# RPI_drawing.net
KiCad netlist of a schematic drawn in Altium Designer
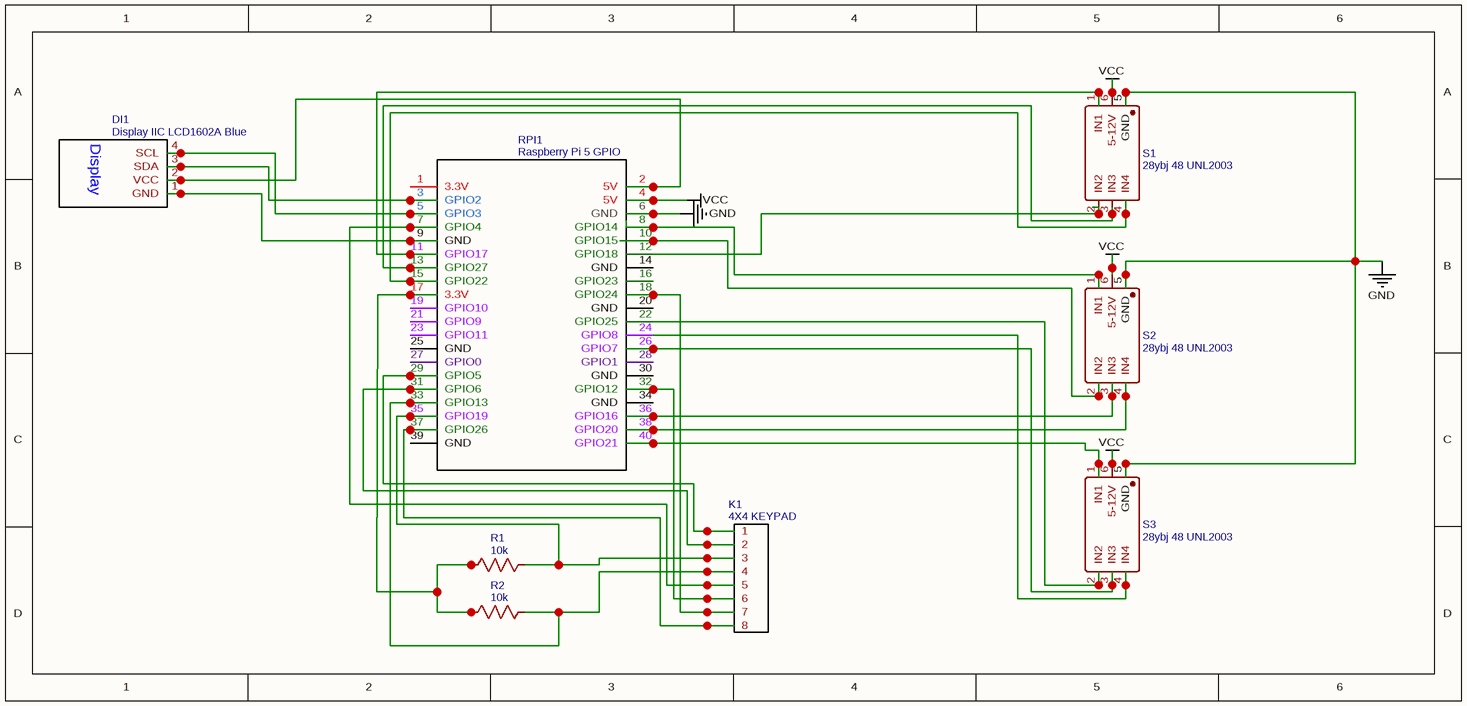
[diagram p0: RPI_drawing.schdoc]

(export (version "E")
  (design (tool "Eeschema 10.0.6"))
  (components
    (comp (ref "DI1")
      (value "Display IIC LCD1602A Blue")
      (fields (field (name "CONTRIBUTOR") "ziclope"))
      (libsource (lib "altium-import") (part "root_2_Display IIC LCD1602A Blue_"))
    )
    (comp (ref "K1")
      (value "4X4 KEYPAD")
      (fields (field (name "CONTRIBUTOR") "hasbifajrul03"))
      (libsource (lib "altium-import") (part "root_3_4X4 KEYPAD_"))
    )
    (comp (ref "R1")
      (value "10k")
      (fields (field (name "CONTRIBUTOR") "LCEDA_Lib"))
      (libsource (lib "altium-import") (part "root_0_10k_"))
    )
    (comp (ref "R2")
      (value "10k")
      (fields (field (name "CONTRIBUTOR") "LCEDA_Lib"))
      (libsource (lib "altium-import") (part "root_0_10k_"))
    )
    (comp (ref "RPI1")
      (value "Raspberry Pi 5 GPIO")
      (fields
        (field (name "MANUFACTURER") "Raspberry Pi 5 4GB")
        (field (name "CONTRIBUTOR") "marcus06second")
      )
      (libsource (lib "altium-import") (part "root_0_Raspberry Pi 5 GPIO_"))
    )
    (comp (ref "S1")
      (value "28ybj 48 UNL2003")
      (fields (field (name "CONTRIBUTOR") "amenard"))
      (libsource (lib "altium-import") (part "root_3_28ybj 48 UNL2003_"))
    )
    (comp (ref "S2")
      (value "28ybj 48 UNL2003")
      (fields (field (name "CONTRIBUTOR") "amenard"))
      (libsource (lib "altium-import") (part "root_3_28ybj 48 UNL2003_"))
    )
    (comp (ref "S3")
      (value "28ybj 48 UNL2003")
      (fields (field (name "CONTRIBUTOR") "amenard"))
      (libsource (lib "altium-import") (part "root_3_28ybj 48 UNL2003_"))
    )
  )
  (nets
    (net (code "1") (name "GND") (class "Default")
      (node (ref "RPI1") (pin "6") (pinfunction "GND_6") (pintype "passive"))
      (node (ref "S1") (pin "5") (pinfunction "GND_5") (pintype "passive"))
      (node (ref "S2") (pin "5") (pinfunction "GND_5") (pintype "passive"))
      (node (ref "S3") (pin "5") (pinfunction "GND_5") (pintype "passive"))
    )
    (net (code "2") (name "Net-(DI1-GND)") (class "Default")
      (node (ref "DI1") (pin "1") (pinfunction "GND_1") (pintype "passive"))
      (node (ref "RPI1") (pin "9") (pinfunction "GND_9") (pintype "passive"))
    )
    (net (code "3") (name "Net-(DI1-SCL)") (class "Default")
      (node (ref "DI1") (pin "4") (pinfunction "SCL_4") (pintype "passive"))
      (node (ref "RPI1") (pin "5") (pinfunction "GPIO3_5") (pintype "passive"))
    )
    (net (code "4") (name "Net-(DI1-SDA)") (class "Default")
      (node (ref "DI1") (pin "3") (pinfunction "SDA_3") (pintype "passive"))
      (node (ref "RPI1") (pin "3") (pinfunction "GPIO2_3") (pintype "passive"))
    )
    (net (code "5") (name "Net-(DI1-VCC)") (class "Default")
      (node (ref "DI1") (pin "2") (pinfunction "VCC_2") (pintype "passive"))
      (node (ref "RPI1") (pin "2") (pinfunction "5V_2") (pintype "passive"))
    )
    (net (code "6") (name "Net-(K1-1)") (class "Default")
      (node (ref "K1") (pin "3") (pinfunction "1_3") (pintype "passive"))
      (node (ref "RPI1") (pin "29") (pinfunction "GPIO5_29") (pintype "passive"))
    )
    (net (code "7") (name "Net-(K1-2)") (class "Default")
      (node (ref "K1") (pin "4") (pinfunction "2_4") (pintype "passive"))
      (node (ref "RPI1") (pin "31") (pinfunction "GPIO6_31") (pintype "passive"))
    )
    (net (code "8") (name "Net-(K1-3)") (class "Default")
      (node (ref "K1") (pin "5") (pinfunction "3_5") (pintype "passive"))
      (node (ref "R1") (pin "2") (pinfunction "2_2") (pintype "passive"))
      (node (ref "RPI1") (pin "35") (pinfunction "GPIO19_35") (pintype "passive"))
    )
    (net (code "9") (name "Net-(K1-4)") (class "Default")
      (node (ref "K1") (pin "6") (pinfunction "4_6") (pintype "passive"))
      (node (ref "R2") (pin "2") (pinfunction "2_2") (pintype "passive"))
      (node (ref "RPI1") (pin "33") (pinfunction "GPIO13_33") (pintype "passive"))
    )
    (net (code "10") (name "Net-(K1-5)") (class "Default")
      (node (ref "K1") (pin "7") (pinfunction "5_7") (pintype "passive"))
      (node (ref "RPI1") (pin "7") (pinfunction "GPIO4_7") (pintype "passive"))
    )
    (net (code "11") (name "Net-(K1-6)") (class "Default")
      (node (ref "K1") (pin "8") (pinfunction "6_8") (pintype "passive"))
      (node (ref "RPI1") (pin "32") (pinfunction "GPIO12_32") (pintype "passive"))
    )
    (net (code "12") (name "Net-(K1-7)") (class "Default")
      (node (ref "K1") (pin "9") (pinfunction "7_9") (pintype "passive"))
      (node (ref "RPI1") (pin "18") (pinfunction "GPIO24_18") (pintype "passive"))
    )
    (net (code "13") (name "Net-(K1-8)") (class "Default")
      (node (ref "K1") (pin "10") (pinfunction "8_10") (pintype "passive"))
      (node (ref "RPI1") (pin "37") (pinfunction "GPIO26_37") (pintype "passive"))
    )
    (net (code "14") (name "Net-(R1-Pad1)") (class "Default")
      (node (ref "R1") (pin "1") (pinfunction "1_1") (pintype "passive"))
      (node (ref "R2") (pin "1") (pinfunction "1_1") (pintype "passive"))
      (node (ref "RPI1") (pin "17") (pinfunction "3.3V_17") (pintype "passive"))
    )
    (net (code "15") (name "Net-(RPI1-GPIO7)") (class "Default")
      (node (ref "RPI1") (pin "26") (pinfunction "GPIO7_26") (pintype "passive"))
      (node (ref "S3") (pin "3") (pinfunction "IN3_3") (pintype "passive"))
    )
    (net (code "16") (name "Net-(RPI1-GPIO8)") (class "Default")
      (node (ref "RPI1") (pin "24") (pinfunction "GPIO8_24") (pintype "passive"))
      (node (ref "S3") (pin "4") (pinfunction "IN4_4") (pintype "passive"))
    )
    (net (code "17") (name "Net-(RPI1-GPIO14)") (class "Default")
      (node (ref "RPI1") (pin "8") (pinfunction "GPIO14_8") (pintype "passive"))
      (node (ref "S2") (pin "1") (pinfunction "IN1_1") (pintype "passive"))
    )
    (net (code "18") (name "Net-(RPI1-GPIO15)") (class "Default")
      (node (ref "RPI1") (pin "10") (pinfunction "GPIO15_10") (pintype "passive"))
      (node (ref "S2") (pin "2") (pinfunction "IN2_2") (pintype "passive"))
    )
    (net (code "19") (name "Net-(RPI1-GPIO16)") (class "Default")
      (node (ref "RPI1") (pin "36") (pinfunction "GPIO16_36") (pintype "passive"))
      (node (ref "S2") (pin "3") (pinfunction "IN3_3") (pintype "passive"))
    )
    (net (code "20") (name "Net-(RPI1-GPIO17)") (class "Default")
      (node (ref "RPI1") (pin "11") (pinfunction "GPIO17_11") (pintype "passive"))
      (node (ref "S1") (pin "1") (pinfunction "IN1_1") (pintype "passive"))
    )
    (net (code "21") (name "Net-(RPI1-GPIO18)") (class "Default")
      (node (ref "RPI1") (pin "12") (pinfunction "GPIO18_12") (pintype "passive"))
      (node (ref "S1") (pin "2") (pinfunction "IN2_2") (pintype "passive"))
    )
    (net (code "22") (name "Net-(RPI1-GPIO20)") (class "Default")
      (node (ref "RPI1") (pin "38") (pinfunction "GPIO20_38") (pintype "passive"))
      (node (ref "S2") (pin "4") (pinfunction "IN4_4") (pintype "passive"))
    )
    (net (code "23") (name "Net-(RPI1-GPIO21)") (class "Default")
      (node (ref "RPI1") (pin "40") (pinfunction "GPIO21_40") (pintype "passive"))
      (node (ref "S3") (pin "1") (pinfunction "IN1_1") (pintype "passive"))
    )
    (net (code "24") (name "Net-(RPI1-GPIO22)") (class "Default")
      (node (ref "RPI1") (pin "15") (pinfunction "GPIO22_15") (pintype "passive"))
      (node (ref "S1") (pin "4") (pinfunction "IN4_4") (pintype "passive"))
    )
    (net (code "25") (name "Net-(RPI1-GPIO25)") (class "Default")
      (node (ref "RPI1") (pin "22") (pinfunction "GPIO25_22") (pintype "passive"))
      (node (ref "S3") (pin "2") (pinfunction "IN2_2") (pintype "passive"))
    )
    (net (code "26") (name "Net-(RPI1-GPIO27)") (class "Default")
      (node (ref "RPI1") (pin "13") (pinfunction "GPIO27_13") (pintype "passive"))
      (node (ref "S1") (pin "3") (pinfunction "IN3_3") (pintype "passive"))
    )
    (net (code "27") (name "VCC") (class "Default")
      (node (ref "RPI1") (pin "4") (pinfunction "5V_4") (pintype "passive"))
      (node (ref "S1") (pin "6") (pinfunction "5-12V_6") (pintype "passive"))
      (node (ref "S2") (pin "6") (pinfunction "5-12V_6") (pintype "passive"))
      (node (ref "S3") (pin "6") (pinfunction "5-12V_6") (pintype "passive"))
    )
    (net (code "28") (name "unconnected-(RPI1-3.3V-Pad1)") (class "Default")
      (node (ref "RPI1") (pin "1") (pinfunction "3.3V_1") (pintype "passive"))
    )
    (net (code "29") (name "unconnected-(RPI1-GND-Pad14)") (class "Default")
      (node (ref "RPI1") (pin "14") (pinfunction "GND_14") (pintype "passive"))
    )
    (net (code "30") (name "unconnected-(RPI1-GND-Pad20)") (class "Default")
      (node (ref "RPI1") (pin "20") (pinfunction "GND_20") (pintype "passive"))
    )
    (net (code "31") (name "unconnected-(RPI1-GND-Pad25)") (class "Default")
      (node (ref "RPI1") (pin "25") (pinfunction "GND_25") (pintype "passive"))
    )
    (net (code "32") (name "unconnected-(RPI1-GND-Pad30)") (class "Default")
      (node (ref "RPI1") (pin "30") (pinfunction "GND_30") (pintype "passive"))
    )
    (net (code "33") (name "unconnected-(RPI1-GND-Pad34)") (class "Default")
      (node (ref "RPI1") (pin "34") (pinfunction "GND_34") (pintype "passive"))
    )
    (net (code "34") (name "unconnected-(RPI1-GND-Pad39)") (class "Default")
      (node (ref "RPI1") (pin "39") (pinfunction "GND_39") (pintype "passive"))
    )
    (net (code "35") (name "unconnected-(RPI1-GPIO0-Pad27)") (class "Default")
      (node (ref "RPI1") (pin "27") (pinfunction "GPIO0_27") (pintype "passive"))
    )
    (net (code "36") (name "unconnected-(RPI1-GPIO1-Pad28)") (class "Default")
      (node (ref "RPI1") (pin "28") (pinfunction "GPIO1_28") (pintype "passive"))
    )
    (net (code "37") (name "unconnected-(RPI1-GPIO9-Pad21)") (class "Default")
      (node (ref "RPI1") (pin "21") (pinfunction "GPIO9_21") (pintype "passive"))
    )
    (net (code "38") (name "unconnected-(RPI1-GPIO10-Pad19)") (class "Default")
      (node (ref "RPI1") (pin "19") (pinfunction "GPIO10_19") (pintype "passive"))
    )
    (net (code "39") (name "unconnected-(RPI1-GPIO11-Pad23)") (class "Default")
      (node (ref "RPI1") (pin "23") (pinfunction "GPIO11_23") (pintype "passive"))
    )
    (net (code "40") (name "unconnected-(RPI1-GPIO23-Pad16)") (class "Default")
      (node (ref "RPI1") (pin "16") (pinfunction "GPIO23_16") (pintype "passive"))
    )
  )
)
